# werkstatt-exp.net
KiCad netlist of a schematic drawn in EAGLE
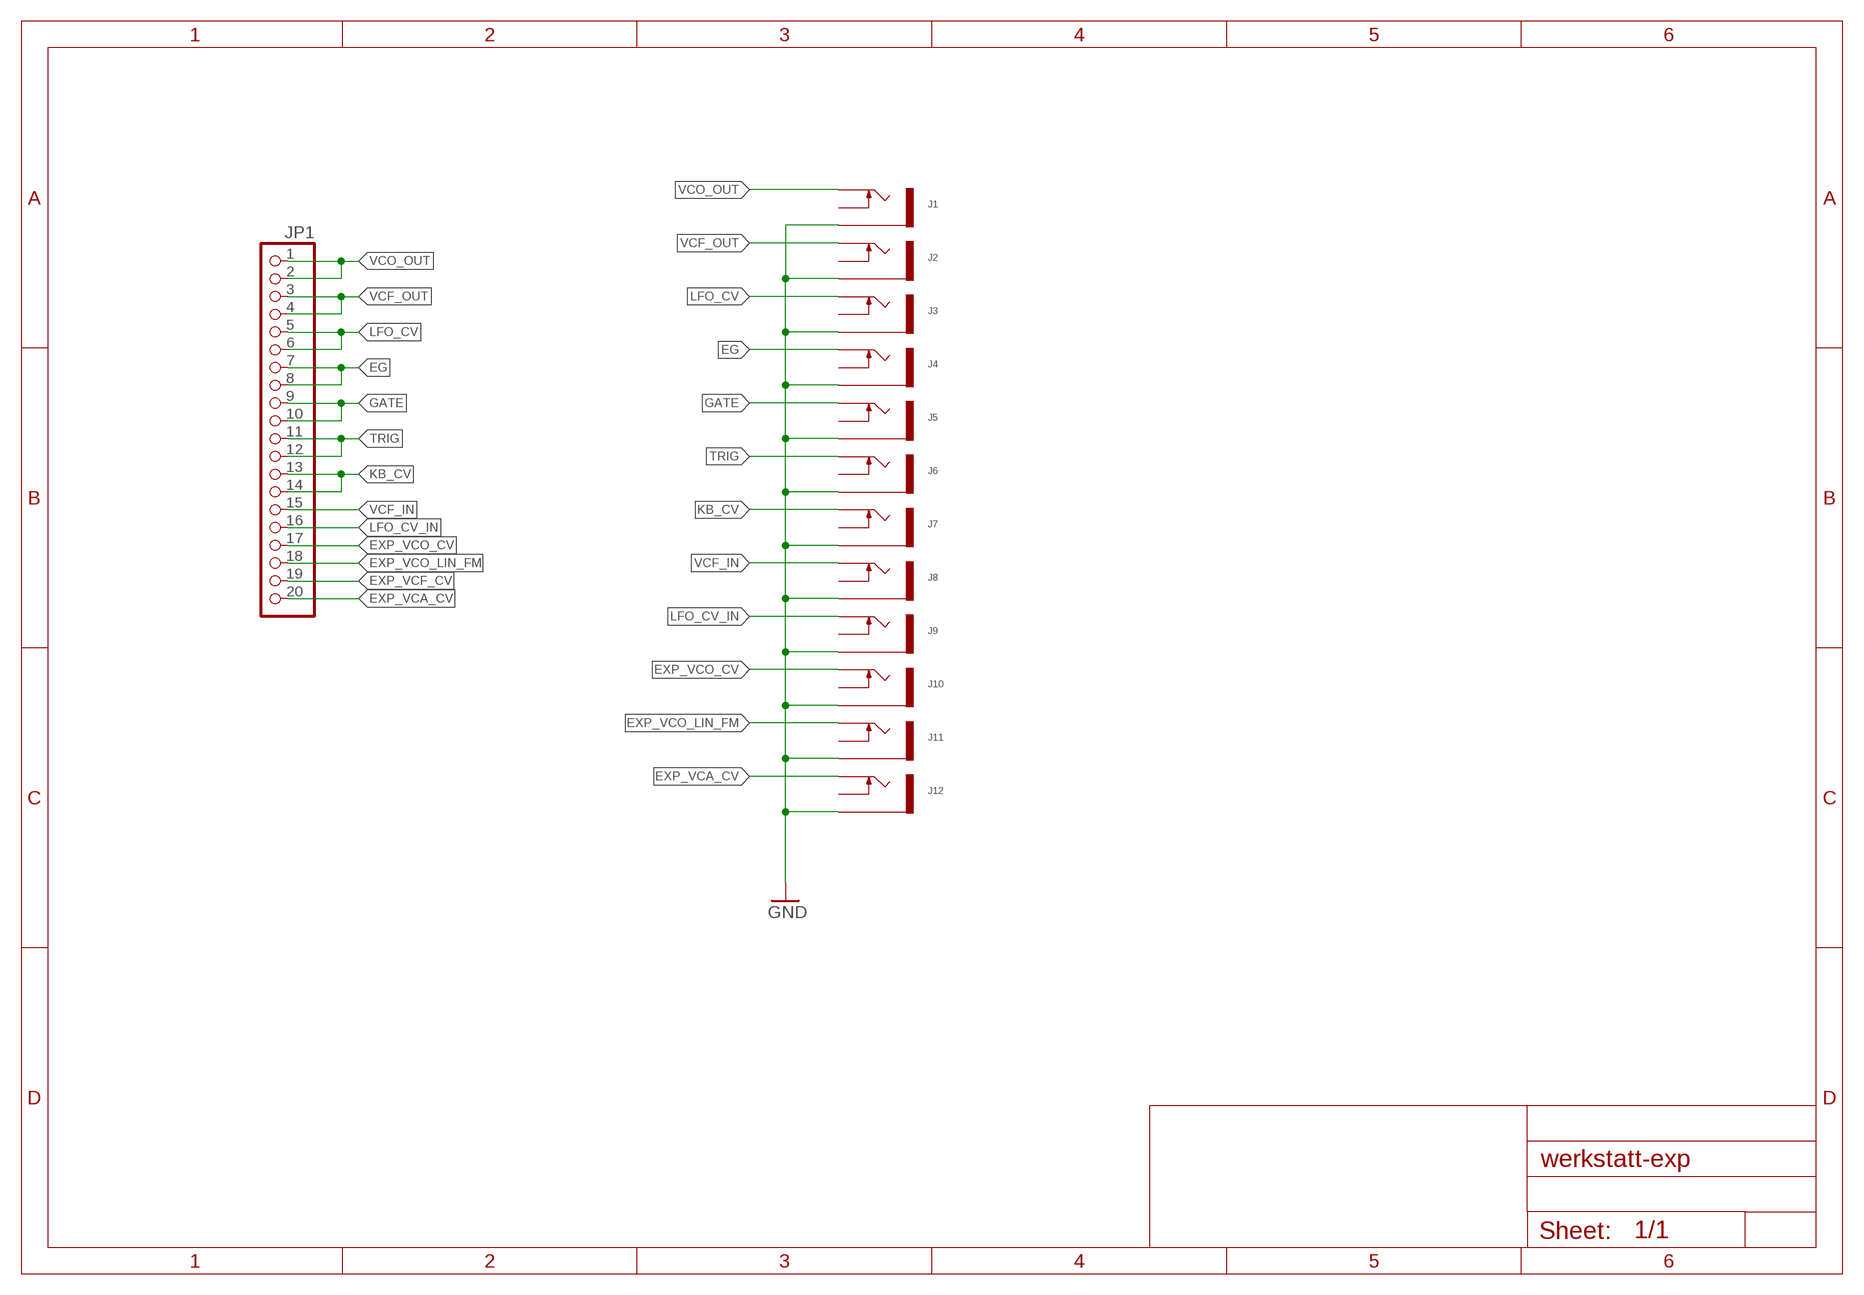
[diagram p0: schematic, sheet 1]

(export (version "E")
  (design (tool "Eeschema 10.0.6"))
  (components
    (comp (ref "J1")
      (value "THONKICON")
      (footprint "eagle-import:WQP-PJ301M-12_JACK")
      (libsource (lib "eagle-import") (part "THONKICON"))
    )
    (comp (ref "J2")
      (value "THONKICON")
      (footprint "eagle-import:WQP-PJ301M-12_JACK")
      (libsource (lib "eagle-import") (part "THONKICON"))
    )
    (comp (ref "J3")
      (value "THONKICON")
      (footprint "eagle-import:WQP-PJ301M-12_JACK")
      (libsource (lib "eagle-import") (part "THONKICON"))
    )
    (comp (ref "J4")
      (value "THONKICON")
      (footprint "eagle-import:WQP-PJ301M-12_JACK")
      (libsource (lib "eagle-import") (part "THONKICON"))
    )
    (comp (ref "J5")
      (value "THONKICON")
      (footprint "eagle-import:WQP-PJ301M-12_JACK")
      (libsource (lib "eagle-import") (part "THONKICON"))
    )
    (comp (ref "J6")
      (value "THONKICON")
      (footprint "eagle-import:WQP-PJ301M-12_JACK")
      (libsource (lib "eagle-import") (part "THONKICON"))
    )
    (comp (ref "J7")
      (value "THONKICON")
      (footprint "eagle-import:WQP-PJ301M-12_JACK")
      (libsource (lib "eagle-import") (part "THONKICON"))
    )
    (comp (ref "J8")
      (value "THONKICON")
      (footprint "eagle-import:WQP-PJ301M-12_JACK")
      (libsource (lib "eagle-import") (part "THONKICON"))
    )
    (comp (ref "J9")
      (value "THONKICON")
      (footprint "eagle-import:WQP-PJ301M-12_JACK")
      (libsource (lib "eagle-import") (part "THONKICON"))
    )
    (comp (ref "J10")
      (value "THONKICON")
      (footprint "eagle-import:WQP-PJ301M-12_JACK")
      (libsource (lib "eagle-import") (part "THONKICON"))
    )
    (comp (ref "J11")
      (value "THONKICON")
      (footprint "eagle-import:WQP-PJ301M-12_JACK")
      (libsource (lib "eagle-import") (part "THONKICON"))
    )
    (comp (ref "J12")
      (value "THONKICON")
      (footprint "eagle-import:WQP-PJ301M-12_JACK")
      (libsource (lib "eagle-import") (part "THONKICON"))
    )
    (comp (ref "JP1")
      (value "PINHD-1X20")
      (footprint "eagle-import:1X20")
      (libsource (lib "eagle-import") (part "PINHD-1X20"))
    )
  )
  (nets
    (net (code "1") (name "EG") (class "Default")
      (node (ref "J4") (pin "3") (pinfunction "2_3") (pintype "passive"))
      (node (ref "JP1") (pin "7") (pinfunction "7_7") (pintype "passive"))
      (node (ref "JP1") (pin "8") (pinfunction "8_8") (pintype "passive"))
    )
    (net (code "2") (name "EXP_VCA_CV") (class "Default")
      (node (ref "J12") (pin "3") (pinfunction "2_3") (pintype "passive"))
      (node (ref "JP1") (pin "20") (pinfunction "20_20") (pintype "passive"))
    )
    (net (code "3") (name "EXP_VCF_CV") (class "Default")
      (node (ref "JP1") (pin "19") (pinfunction "19_19") (pintype "passive"))
    )
    (net (code "4") (name "EXP_VCO_CV") (class "Default")
      (node (ref "J10") (pin "3") (pinfunction "2_3") (pintype "passive"))
      (node (ref "JP1") (pin "17") (pinfunction "17_17") (pintype "passive"))
    )
    (net (code "5") (name "EXP_VCO_LIN_FM") (class "Default")
      (node (ref "J11") (pin "3") (pinfunction "2_3") (pintype "passive"))
      (node (ref "JP1") (pin "18") (pinfunction "18_18") (pintype "passive"))
    )
    (net (code "6") (name "GATE") (class "Default")
      (node (ref "J5") (pin "3") (pinfunction "2_3") (pintype "passive"))
      (node (ref "JP1") (pin "10") (pinfunction "10_10") (pintype "passive"))
      (node (ref "JP1") (pin "9") (pinfunction "9_9") (pintype "passive"))
    )
    (net (code "7") (name "GND") (class "Default")
      (node (ref "J1") (pin "1") (pinfunction "1_1") (pintype "passive"))
      (node (ref "J10") (pin "1") (pinfunction "1_1") (pintype "passive"))
      (node (ref "J11") (pin "1") (pinfunction "1_1") (pintype "passive"))
      (node (ref "J12") (pin "1") (pinfunction "1_1") (pintype "passive"))
      (node (ref "J2") (pin "1") (pinfunction "1_1") (pintype "passive"))
      (node (ref "J3") (pin "1") (pinfunction "1_1") (pintype "passive"))
      (node (ref "J4") (pin "1") (pinfunction "1_1") (pintype "passive"))
      (node (ref "J5") (pin "1") (pinfunction "1_1") (pintype "passive"))
      (node (ref "J6") (pin "1") (pinfunction "1_1") (pintype "passive"))
      (node (ref "J7") (pin "1") (pinfunction "1_1") (pintype "passive"))
      (node (ref "J8") (pin "1") (pinfunction "1_1") (pintype "passive"))
      (node (ref "J9") (pin "1") (pinfunction "1_1") (pintype "passive"))
    )
    (net (code "8") (name "KB_CV") (class "Default")
      (node (ref "J7") (pin "3") (pinfunction "2_3") (pintype "passive"))
      (node (ref "JP1") (pin "13") (pinfunction "13_13") (pintype "passive"))
      (node (ref "JP1") (pin "14") (pinfunction "14_14") (pintype "passive"))
    )
    (net (code "9") (name "LFO_CV") (class "Default")
      (node (ref "J3") (pin "3") (pinfunction "2_3") (pintype "passive"))
      (node (ref "JP1") (pin "5") (pinfunction "5_5") (pintype "passive"))
      (node (ref "JP1") (pin "6") (pinfunction "6_6") (pintype "passive"))
    )
    (net (code "10") (name "LFO_CV_IN") (class "Default")
      (node (ref "J9") (pin "3") (pinfunction "2_3") (pintype "passive"))
      (node (ref "JP1") (pin "16") (pinfunction "16_16") (pintype "passive"))
    )
    (net (code "11") (name "TRIG") (class "Default")
      (node (ref "J6") (pin "3") (pinfunction "2_3") (pintype "passive"))
      (node (ref "JP1") (pin "11") (pinfunction "11_11") (pintype "passive"))
      (node (ref "JP1") (pin "12") (pinfunction "12_12") (pintype "passive"))
    )
    (net (code "12") (name "VCF_IN") (class "Default")
      (node (ref "J8") (pin "3") (pinfunction "2_3") (pintype "passive"))
      (node (ref "JP1") (pin "15") (pinfunction "15_15") (pintype "passive"))
    )
    (net (code "13") (name "VCF_OUT") (class "Default")
      (node (ref "J2") (pin "3") (pinfunction "2_3") (pintype "passive"))
      (node (ref "JP1") (pin "3") (pinfunction "3_3") (pintype "passive"))
      (node (ref "JP1") (pin "4") (pinfunction "4_4") (pintype "passive"))
    )
    (net (code "14") (name "VCO_OUT") (class "Default")
      (node (ref "J1") (pin "3") (pinfunction "2_3") (pintype "passive"))
      (node (ref "JP1") (pin "1") (pinfunction "1_1") (pintype "passive"))
      (node (ref "JP1") (pin "2") (pinfunction "2_2") (pintype "passive"))
    )
    (net (code "15") (name "unconnected-(J1-3-Pad2)") (class "Default")
      (node (ref "J1") (pin "2") (pinfunction "3_2") (pintype "passive"))
    )
    (net (code "16") (name "unconnected-(J2-3-Pad2)") (class "Default")
      (node (ref "J2") (pin "2") (pinfunction "3_2") (pintype "passive"))
    )
    (net (code "17") (name "unconnected-(J3-3-Pad2)") (class "Default")
      (node (ref "J3") (pin "2") (pinfunction "3_2") (pintype "passive"))
    )
    (net (code "18") (name "unconnected-(J4-3-Pad2)") (class "Default")
      (node (ref "J4") (pin "2") (pinfunction "3_2") (pintype "passive"))
    )
    (net (code "19") (name "unconnected-(J5-3-Pad2)") (class "Default")
      (node (ref "J5") (pin "2") (pinfunction "3_2") (pintype "passive"))
    )
    (net (code "20") (name "unconnected-(J6-3-Pad2)") (class "Default")
      (node (ref "J6") (pin "2") (pinfunction "3_2") (pintype "passive"))
    )
    (net (code "21") (name "unconnected-(J7-3-Pad2)") (class "Default")
      (node (ref "J7") (pin "2") (pinfunction "3_2") (pintype "passive"))
    )
    (net (code "22") (name "unconnected-(J8-3-Pad2)") (class "Default")
      (node (ref "J8") (pin "2") (pinfunction "3_2") (pintype "passive"))
    )
    (net (code "23") (name "unconnected-(J9-3-Pad2)") (class "Default")
      (node (ref "J9") (pin "2") (pinfunction "3_2") (pintype "passive"))
    )
    (net (code "24") (name "unconnected-(J10-3-Pad2)") (class "Default")
      (node (ref "J10") (pin "2") (pinfunction "3_2") (pintype "passive"))
    )
    (net (code "25") (name "unconnected-(J11-3-Pad2)") (class "Default")
      (node (ref "J11") (pin "2") (pinfunction "3_2") (pintype "passive"))
    )
    (net (code "26") (name "unconnected-(J12-3-Pad2)") (class "Default")
      (node (ref "J12") (pin "2") (pinfunction "3_2") (pintype "passive"))
    )
  )
)
